# LNA.net
KiCad netlist of a schematic drawn in Altium Designer
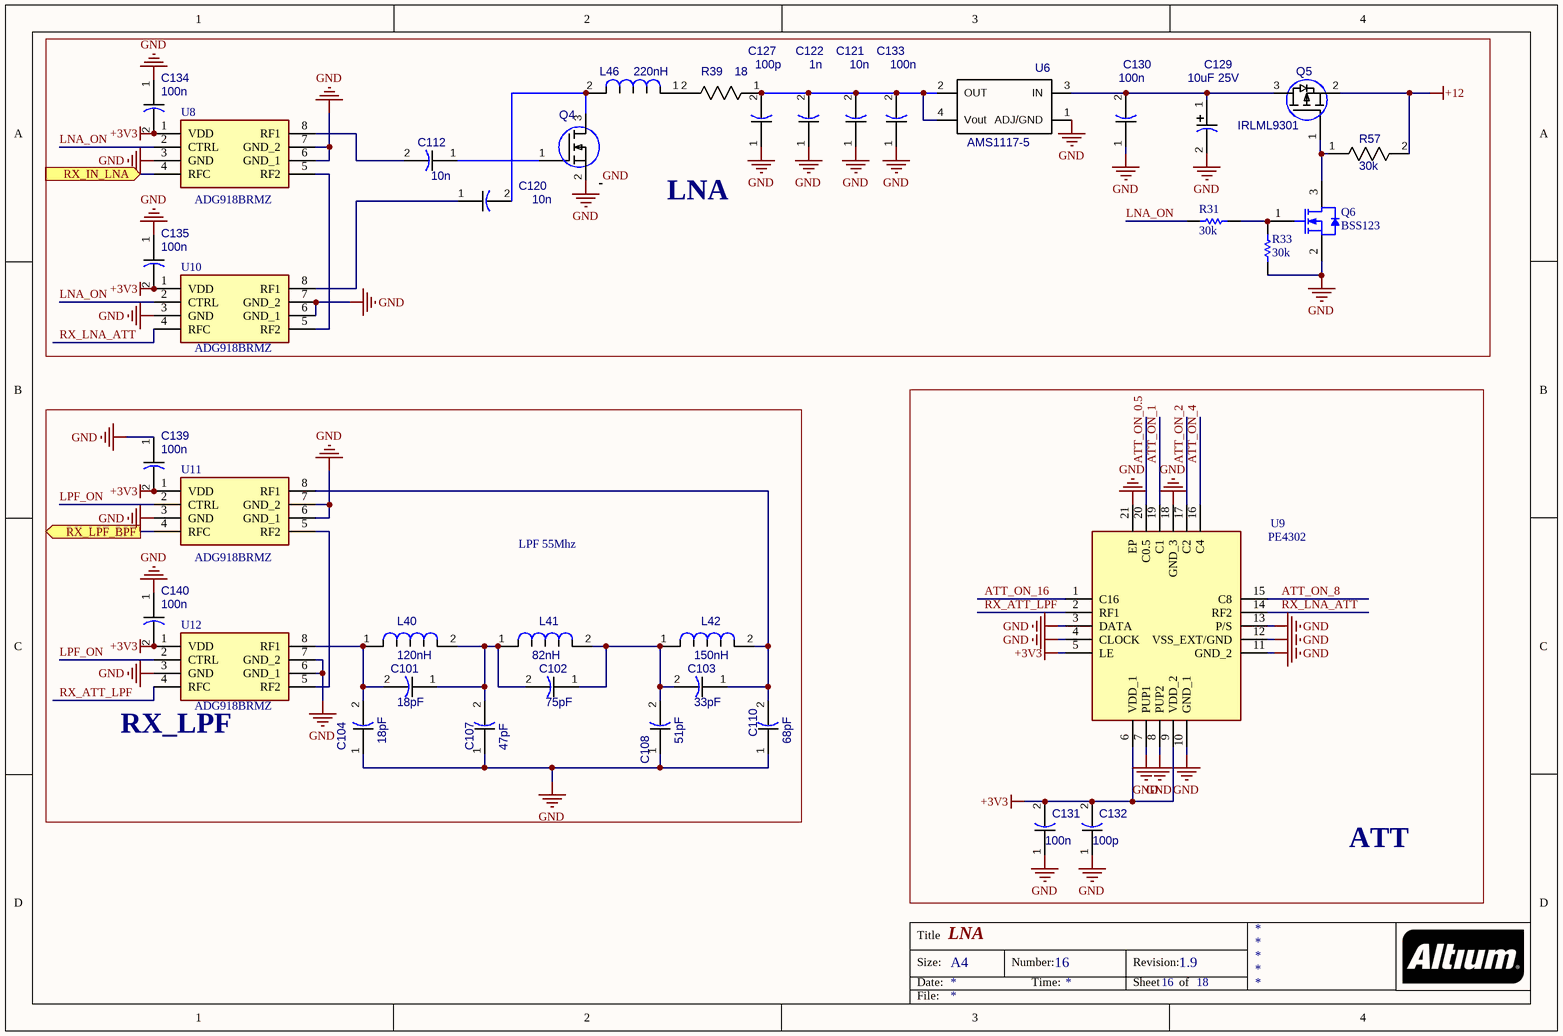
[diagram p0: LNA.SchDoc]

(export (version "E")
  (design (tool "Eeschema 10.0.6"))
  (components
    (comp (ref "C101")
      (value "18pF")
      (footprint "CAP_0805")
      (description "CAP_0805")
      (libsource (lib "*") (part "CAP_0805"))
    )
    (comp (ref "C102")
      (value "75pF")
      (footprint "CAP_0805")
      (description "CAP_0805")
      (libsource (lib "*") (part "CAP_0805"))
    )
    (comp (ref "C103")
      (value "33pF")
      (footprint "CAP_0805")
      (description "CAP_0805")
      (libsource (lib "*") (part "CAP_0805"))
    )
    (comp (ref "C104")
      (value "18pF")
      (footprint "CAP_0805")
      (description "CAP_0805")
      (libsource (lib "*") (part "CAP_0805"))
    )
    (comp (ref "C107")
      (value "47pF")
      (footprint "CAP_0805")
      (description "CAP_0805")
      (libsource (lib "*") (part "CAP_0805"))
    )
    (comp (ref "C108")
      (value "51pF")
      (footprint "CAP_0805")
      (description "CAP_0805")
      (libsource (lib "*") (part "CAP_0805"))
    )
    (comp (ref "C110")
      (value "68pF")
      (footprint "CAP_0805")
      (description "CAP_0805")
      (libsource (lib "*") (part "CAP_0805"))
    )
    (comp (ref "C112")
      (value "10n")
      (footprint "CAP_0805")
      (description "CAP_0805")
      (libsource (lib "*") (part "CAP_0805"))
    )
    (comp (ref "C120")
      (value "10n")
      (footprint "CAP_0805")
      (description "CAP_0805")
      (libsource (lib "*") (part "CAP_0805"))
    )
    (comp (ref "C121")
      (value "10n")
      (footprint "6-0805_M")
      (description "CAP_0805")
      (libsource (lib "*") (part "CAP_0805"))
    )
    (comp (ref "C122")
      (value "1n")
      (footprint "6-0805_M")
      (description "CAP_0805")
      (libsource (lib "*") (part "CAP_0805"))
    )
    (comp (ref "C127")
      (value "100p")
      (footprint "6-0805_M")
      (description "CAP_0805")
      (libsource (lib "*") (part "CAP_0805"))
    )
    (comp (ref "C129")
      (value "10uF 25V")
      (footprint "CAPAE_5.3x5.3h6.1")
      (description "CAPAE_5.3x5.3h6.1")
      (libsource (lib "*") (part "CAPAE_5.3x5.3h6.1"))
    )
    (comp (ref "C130")
      (value "100n")
      (footprint "CAP_0805")
      (description "CAP_0805")
      (libsource (lib "") (part "CAP_0805_1"))
    )
    (comp (ref "C131")
      (value "100n")
      (footprint "6-0805_M")
      (description "CAP_0805")
      (libsource (lib "*") (part "CAP_0805"))
    )
    (comp (ref "C132")
      (value "100p")
      (footprint "6-0805_M")
      (description "CAP_0805")
      (libsource (lib "*") (part "CAP_0805"))
    )
    (comp (ref "C133")
      (value "100n")
      (footprint "CAP_0805")
      (description "CAP_0805")
      (libsource (lib "*") (part "CAP_0805"))
    )
    (comp (ref "C134")
      (value "100n")
      (footprint "CAP_0805")
      (description "CAP_0805")
      (libsource (lib "*") (part "CAP_0805"))
    )
    (comp (ref "C135")
      (value "100n")
      (footprint "CAP_0805")
      (description "CAP_0805")
      (libsource (lib "*") (part "CAP_0805"))
    )
    (comp (ref "C139")
      (value "100n")
      (footprint "CAP_0805")
      (description "CAP_0805")
      (libsource (lib "*") (part "CAP_0805"))
    )
    (comp (ref "C140")
      (value "100n")
      (footprint "CAP_0805")
      (description "CAP_0805")
      (libsource (lib "*") (part "CAP_0805"))
    )
    (comp (ref "L40")
      (value "120nH")
      (footprint "IND_0805")
      (description "IND_0805")
      (libsource (lib "*") (part "IND_0805"))
    )
    (comp (ref "L41")
      (value "82nH")
      (footprint "IND_0805")
      (description "IND_0805")
      (libsource (lib "*") (part "IND_0805"))
    )
    (comp (ref "L42")
      (value "150nH")
      (footprint "IND_0805")
      (description "IND_0805")
      (libsource (lib "*") (part "IND_0805"))
    )
    (comp (ref "L46")
      (value "220nH")
      (footprint "IND_1206")
      (description "IND_1206")
      (libsource (lib "*") (part "IND_1206"))
    )
    (comp (ref "Q4")
      (value "PGA-103+")
      (footprint "SOT89")
      (description "MOSFET")
      (libsource (lib "*") (part "PGA-103+"))
    )
    (comp (ref "Q5")
      (value "IRLML9301")
      (footprint "SOT23")
      (description "MOSFET")
      (libsource (lib "*") (part "MOSFET_ENH_PD"))
    )
    (comp (ref "Q6")
      (value "BSS123")
      (footprint "FAIR-SOT23-3_V")
      (fields (field (name "MANUFACTURER") "Fairchild"))
      (libsource (lib "Altium Content Vault") (part "NEMOS-GSD-3"))
    )
    (comp (ref "R31")
      (value "30k")
      (footprint "RESC2013X60X40NL20T25")
      (description "RES_0805")
      (fields (field (name "MANUFACTURER") "Panasonic") (field (name "PART NUMBER") "ERA-6AEB303V"))
      (libsource (lib "Altium Content Vault") (part "RES"))
    )
    (comp (ref "R33")
      (value "30k")
      (footprint "RESC2013X60X40NL20T25")
      (description "RES_0805")
      (fields (field (name "MANUFACTURER") "Panasonic") (field (name "PART NUMBER") "ERA-6AEB303V"))
      (libsource (lib "Altium Content Vault") (part "RES"))
    )
    (comp (ref "R39")
      (value "18")
      (footprint "RES_1206")
      (description "RES_1206")
      (libsource (lib "*") (part "RES_1206"))
    )
    (comp (ref "R57")
      (value "30k")
      (footprint "RES_0805")
      (description "RES_0805")
      (libsource (lib "*") (part "RES_0805"))
    )
    (comp (ref "U6") (value "AMS1117-5") (footprint "AMS1117-5") (libsource (lib "*") (part "AMS1117-5")))
    (comp (ref "U8")
      (value "ADG918BRMZ")
      (footprint "SamacSys:SOP65P490X110-8N")
      (description "Integrated Circuit")
      (fields (field (name "MOUSER PART NUMBER") "584-ADG918BRMZ") (field (name "RS PART NUMBER") "4969212P"))
      (libsource (lib "*") (part "ADG918BRMZ"))
    )
    (comp (ref "U9")
      (value "PE4302")
      (footprint "SamacSys:QFN50P400X400X90-21N")
      (description "Integrated Circuit")
      (fields (field (name "MANUFACTURER_PART_NUMBER") "PE4312C-Z"))
      (libsource (lib "*") (part "PE4312C-Z"))
    )
    (comp (ref "U10")
      (value "ADG918BRMZ")
      (footprint "SamacSys:SOP65P490X110-8N")
      (description "Integrated Circuit")
      (fields (field (name "MOUSER PART NUMBER") "584-ADG918BRMZ") (field (name "RS PART NUMBER") "4969212P"))
      (libsource (lib "*") (part "ADG918BRMZ"))
    )
    (comp (ref "U11")
      (value "ADG918BRMZ")
      (footprint "SamacSys:SOP65P490X110-8N")
      (description "Integrated Circuit")
      (fields (field (name "MOUSER PART NUMBER") "584-ADG918BRMZ") (field (name "RS PART NUMBER") "4969212P"))
      (libsource (lib "*") (part "ADG918BRMZ"))
    )
    (comp (ref "U12")
      (value "ADG918BRMZ")
      (footprint "SamacSys:SOP65P490X110-8N")
      (description "Integrated Circuit")
      (fields (field (name "MOUSER PART NUMBER") "584-ADG918BRMZ") (field (name "RS PART NUMBER") "4969212P"))
      (libsource (lib "*") (part "ADG918BRMZ"))
    )
  )
  (nets
    (net (code "1") (name "+3V3") (class "Default")
      (node (ref "C131") (pin "2") (pinfunction "2_2") (pintype "passive"))
      (node (ref "C132") (pin "2") (pinfunction "2_2") (pintype "passive"))
      (node (ref "C134") (pin "2") (pinfunction "2_2") (pintype "passive"))
      (node (ref "C135") (pin "2") (pinfunction "2_2") (pintype "passive"))
      (node (ref "C139") (pin "2") (pinfunction "2_2") (pintype "passive"))
      (node (ref "C140") (pin "2") (pinfunction "2_2") (pintype "passive"))
      (node (ref "U10") (pin "1") (pinfunction "VDD_1") (pintype "power_in"))
      (node (ref "U11") (pin "1") (pinfunction "VDD_1") (pintype "power_in"))
      (node (ref "U12") (pin "1") (pinfunction "VDD_1") (pintype "power_in"))
      (node (ref "U8") (pin "1") (pinfunction "VDD_1") (pintype "power_in"))
      (node (ref "U9") (pin "5") (pinfunction "LE_5") (pintype "passive"))
      (node (ref "U9") (pin "6") (pinfunction "VDD_1_6") (pintype "passive"))
      (node (ref "U9") (pin "9") (pinfunction "VDD_2_9") (pintype "passive"))
    )
    (net (code "2") (name "+12") (class "Default")
      (node (ref "Q5") (pin "2") (pinfunction "S_2") (pintype "passive"))
      (node (ref "R57") (pin "2") (pinfunction "2_2") (pintype "passive"))
    )
    (net (code "3") (name "/ATT_ON_0.5") (class "Default")
      (node (ref "U9") (pin "20") (pinfunction "C0.5_20") (pintype "passive"))
    )
    (net (code "4") (name "/ATT_ON_1") (class "Default")
      (node (ref "U9") (pin "19") (pinfunction "C1_19") (pintype "passive"))
    )
    (net (code "5") (name "/ATT_ON_2") (class "Default")
      (node (ref "U9") (pin "17") (pinfunction "C2_17") (pintype "passive"))
    )
    (net (code "6") (name "/ATT_ON_4") (class "Default")
      (node (ref "U9") (pin "16") (pinfunction "C4_16") (pintype "passive"))
    )
    (net (code "7") (name "/ATT_ON_8") (class "Default")
      (node (ref "U9") (pin "15") (pinfunction "C8_15") (pintype "passive"))
    )
    (net (code "8") (name "/ATT_ON_16") (class "Default")
      (node (ref "U9") (pin "1") (pinfunction "C16_1") (pintype "passive"))
    )
    (net (code "9") (name "/LNA_ON") (class "Default")
      (node (ref "R31") (pin "2") (pinfunction "2_2") (pintype "passive"))
      (node (ref "U10") (pin "2") (pinfunction "CTRL_2") (pintype "passive"))
      (node (ref "U8") (pin "2") (pinfunction "CTRL_2") (pintype "passive"))
    )
    (net (code "10") (name "/LPF_ON") (class "Default")
      (node (ref "U11") (pin "2") (pinfunction "CTRL_2") (pintype "passive"))
      (node (ref "U12") (pin "2") (pinfunction "CTRL_2") (pintype "passive"))
    )
    (net (code "11") (name "/RX_ATT_LPF") (class "Default")
      (node (ref "U12") (pin "4") (pinfunction "RFC_4") (pintype "passive"))
      (node (ref "U9") (pin "2") (pinfunction "RF1_2") (pintype "passive"))
    )
    (net (code "12") (name "/RX_IN_LNA") (class "Default")
      (node (ref "U8") (pin "4") (pinfunction "RFC_4") (pintype "passive"))
    )
    (net (code "13") (name "/RX_LNA_ATT") (class "Default")
      (node (ref "U10") (pin "4") (pinfunction "RFC_4") (pintype "passive"))
      (node (ref "U9") (pin "14") (pinfunction "RF2_14") (pintype "passive"))
    )
    (net (code "14") (name "/RX_LPF_BPF") (class "Default")
      (node (ref "U11") (pin "4") (pinfunction "RFC_4") (pintype "passive"))
    )
    (net (code "15") (name "GND") (class "Default")
      (node (ref "C104") (pin "1") (pinfunction "1_1") (pintype "passive"))
      (node (ref "C107") (pin "1") (pinfunction "1_1") (pintype "passive"))
      (node (ref "C108") (pin "1") (pinfunction "1_1") (pintype "passive"))
      (node (ref "C110") (pin "1") (pinfunction "1_1") (pintype "passive"))
      (node (ref "C121") (pin "1") (pinfunction "1_1") (pintype "passive"))
      (node (ref "C122") (pin "1") (pinfunction "1_1") (pintype "passive"))
      (node (ref "C127") (pin "1") (pinfunction "1_1") (pintype "passive"))
      (node (ref "C129") (pin "2") (pinfunction "MINUS_2") (pintype "passive"))
      (node (ref "C130") (pin "1") (pinfunction "1_1") (pintype "passive"))
      (node (ref "C131") (pin "1") (pinfunction "1_1") (pintype "passive"))
      (node (ref "C132") (pin "1") (pinfunction "1_1") (pintype "passive"))
      (node (ref "C133") (pin "1") (pinfunction "1_1") (pintype "passive"))
      (node (ref "C134") (pin "1") (pinfunction "1_1") (pintype "passive"))
      (node (ref "C135") (pin "1") (pinfunction "1_1") (pintype "passive"))
      (node (ref "C139") (pin "1") (pinfunction "1_1") (pintype "passive"))
      (node (ref "C140") (pin "1") (pinfunction "1_1") (pintype "passive"))
      (node (ref "Q4") (pin "0") (pinfunction "0_0") (pintype "passive"))
      (node (ref "Q4") (pin "2") (pinfunction "S_2") (pintype "passive"))
      (node (ref "Q6") (pin "2") (pinfunction "S_2") (pintype "passive"))
      (node (ref "R33") (pin "1") (pinfunction "1_1") (pintype "passive"))
      (node (ref "U10") (pin "3") (pinfunction "GND_3") (pintype "power_in"))
      (node (ref "U10") (pin "6") (pinfunction "GND_1_6") (pintype "power_in"))
      (node (ref "U10") (pin "7") (pinfunction "GND_2_7") (pintype "power_in"))
      (node (ref "U11") (pin "3") (pinfunction "GND_3") (pintype "power_in"))
      (node (ref "U11") (pin "6") (pinfunction "GND_1_6") (pintype "power_in"))
      (node (ref "U11") (pin "7") (pinfunction "GND_2_7") (pintype "power_in"))
      (node (ref "U12") (pin "3") (pinfunction "GND_3") (pintype "power_in"))
      (node (ref "U12") (pin "6") (pinfunction "GND_1_6") (pintype "power_in"))
      (node (ref "U12") (pin "7") (pinfunction "GND_2_7") (pintype "power_in"))
      (node (ref "U6") (pin "1") (pinfunction "ADJ/GND_1") (pintype "passive"))
      (node (ref "U8") (pin "3") (pinfunction "GND_3") (pintype "power_in"))
      (node (ref "U8") (pin "6") (pinfunction "GND_1_6") (pintype "power_in"))
      (node (ref "U8") (pin "7") (pinfunction "GND_2_7") (pintype "power_in"))
      (node (ref "U9") (pin "10") (pinfunction "GND_1_10") (pintype "passive"))
      (node (ref "U9") (pin "11") (pinfunction "GND_2_11") (pintype "passive"))
      (node (ref "U9") (pin "12") (pinfunction "VSS_EXT/GND_12") (pintype "passive"))
      (node (ref "U9") (pin "13") (pinfunction "P/S_13") (pintype "passive"))
      (node (ref "U9") (pin "18") (pinfunction "GND_3_18") (pintype "passive"))
      (node (ref "U9") (pin "21") (pinfunction "EP_21") (pintype "passive"))
      (node (ref "U9") (pin "3") (pinfunction "DATA_3") (pintype "passive"))
      (node (ref "U9") (pin "4") (pinfunction "CLOCK_4") (pintype "passive"))
      (node (ref "U9") (pin "7") (pinfunction "PUP1_7") (pintype "passive"))
      (node (ref "U9") (pin "8") (pinfunction "PUP2_8") (pintype "passive"))
    )
    (net (code "16") (name "Net-(C101-Pad1)") (class "Default")
      (node (ref "C101") (pin "1") (pinfunction "1_1") (pintype "passive"))
      (node (ref "C102") (pin "2") (pinfunction "2_2") (pintype "passive"))
      (node (ref "C107") (pin "2") (pinfunction "2_2") (pintype "passive"))
      (node (ref "L40") (pin "2") (pinfunction "2_2") (pintype "passive"))
      (node (ref "L41") (pin "1") (pinfunction "1_1") (pintype "passive"))
    )
    (net (code "17") (name "Net-(C102-Pad1)") (class "Default")
      (node (ref "C102") (pin "1") (pinfunction "1_1") (pintype "passive"))
      (node (ref "C103") (pin "2") (pinfunction "2_2") (pintype "passive"))
      (node (ref "C108") (pin "2") (pinfunction "2_2") (pintype "passive"))
      (node (ref "L41") (pin "2") (pinfunction "2_2") (pintype "passive"))
      (node (ref "L42") (pin "1") (pinfunction "1_1") (pintype "passive"))
    )
    (net (code "18") (name "Net-(C129-PLUS)") (class "Default")
      (node (ref "C129") (pin "1") (pinfunction "PLUS_1") (pintype "passive"))
      (node (ref "C130") (pin "2") (pinfunction "2_2") (pintype "passive"))
      (node (ref "Q5") (pin "3") (pinfunction "D_3") (pintype "passive"))
      (node (ref "U6") (pin "3") (pinfunction "IN_3") (pintype "passive"))
    )
    (net (code "19") (name "Net-(L46-1)") (class "Default")
      (node (ref "C120") (pin "2") (pinfunction "2_2") (pintype "passive"))
      (node (ref "L46") (pin "2") (pinfunction "1_2") (pintype "passive"))
      (node (ref "Q4") (pin "3") (pinfunction "D_3") (pintype "passive"))
    )
    (net (code "20") (name "Net-(L46-2)") (class "Default")
      (node (ref "L46") (pin "1") (pinfunction "2_1") (pintype "passive"))
      (node (ref "R39") (pin "2") (pinfunction "2_2") (pintype "passive"))
    )
    (net (code "21") (name "Net-(Q4-G)") (class "Default")
      (node (ref "C112") (pin "1") (pinfunction "1_1") (pintype "passive"))
      (node (ref "Q4") (pin "1") (pinfunction "G_1") (pintype "passive"))
    )
    (net (code "22") (name "Net-(Q5-G)") (class "Default")
      (node (ref "Q5") (pin "1") (pinfunction "G_1") (pintype "passive"))
      (node (ref "Q6") (pin "3") (pinfunction "D_3") (pintype "passive"))
      (node (ref "R57") (pin "1") (pinfunction "1_1") (pintype "passive"))
    )
    (net (code "23") (name "Net-(Q6-G)") (class "Default")
      (node (ref "Q6") (pin "1") (pinfunction "G_1") (pintype "passive"))
      (node (ref "R31") (pin "1") (pinfunction "1_1") (pintype "passive"))
      (node (ref "R33") (pin "2") (pinfunction "2_2") (pintype "passive"))
    )
    (net (code "24") (name "Net-(U6-OUT)") (class "Default")
      (node (ref "C121") (pin "2") (pinfunction "2_2") (pintype "passive"))
      (node (ref "C122") (pin "2") (pinfunction "2_2") (pintype "passive"))
      (node (ref "C127") (pin "2") (pinfunction "2_2") (pintype "passive"))
      (node (ref "C133") (pin "2") (pinfunction "2_2") (pintype "passive"))
      (node (ref "R39") (pin "1") (pinfunction "1_1") (pintype "passive"))
      (node (ref "U6") (pin "2") (pinfunction "OUT_2") (pintype "passive"))
      (node (ref "U6") (pin "4") (pinfunction "Vout_4") (pintype "passive"))
    )
    (net (code "25") (name "Net-(U8-RF1)") (class "Default")
      (node (ref "C112") (pin "2") (pinfunction "2_2") (pintype "passive"))
      (node (ref "U8") (pin "8") (pinfunction "RF1_8") (pintype "passive"))
    )
    (net (code "26") (name "Net-(U10-RF1)") (class "Default")
      (node (ref "C120") (pin "1") (pinfunction "1_1") (pintype "passive"))
      (node (ref "U10") (pin "8") (pinfunction "RF1_8") (pintype "passive"))
    )
    (net (code "27") (name "Net-(U10-RF2)") (class "Default")
      (node (ref "U10") (pin "5") (pinfunction "RF2_5") (pintype "passive"))
      (node (ref "U8") (pin "5") (pinfunction "RF2_5") (pintype "passive"))
    )
    (net (code "28") (name "Net-(U11-RF1)") (class "Default")
      (node (ref "C103") (pin "1") (pinfunction "1_1") (pintype "passive"))
      (node (ref "C110") (pin "2") (pinfunction "2_2") (pintype "passive"))
      (node (ref "L42") (pin "2") (pinfunction "2_2") (pintype "passive"))
      (node (ref "U11") (pin "8") (pinfunction "RF1_8") (pintype "passive"))
    )
    (net (code "29") (name "Net-(U11-RF2)") (class "Default")
      (node (ref "U11") (pin "5") (pinfunction "RF2_5") (pintype "passive"))
      (node (ref "U12") (pin "5") (pinfunction "RF2_5") (pintype "passive"))
    )
    (net (code "30") (name "Net-(U12-RF1)") (class "Default")
      (node (ref "C101") (pin "2") (pinfunction "2_2") (pintype "passive"))
      (node (ref "C104") (pin "2") (pinfunction "2_2") (pintype "passive"))
      (node (ref "L40") (pin "1") (pinfunction "1_1") (pintype "passive"))
      (node (ref "U12") (pin "8") (pinfunction "RF1_8") (pintype "passive"))
    )
  )
)
